# relay1.net
KiCad netlist of a schematic drawn in Altium Designer
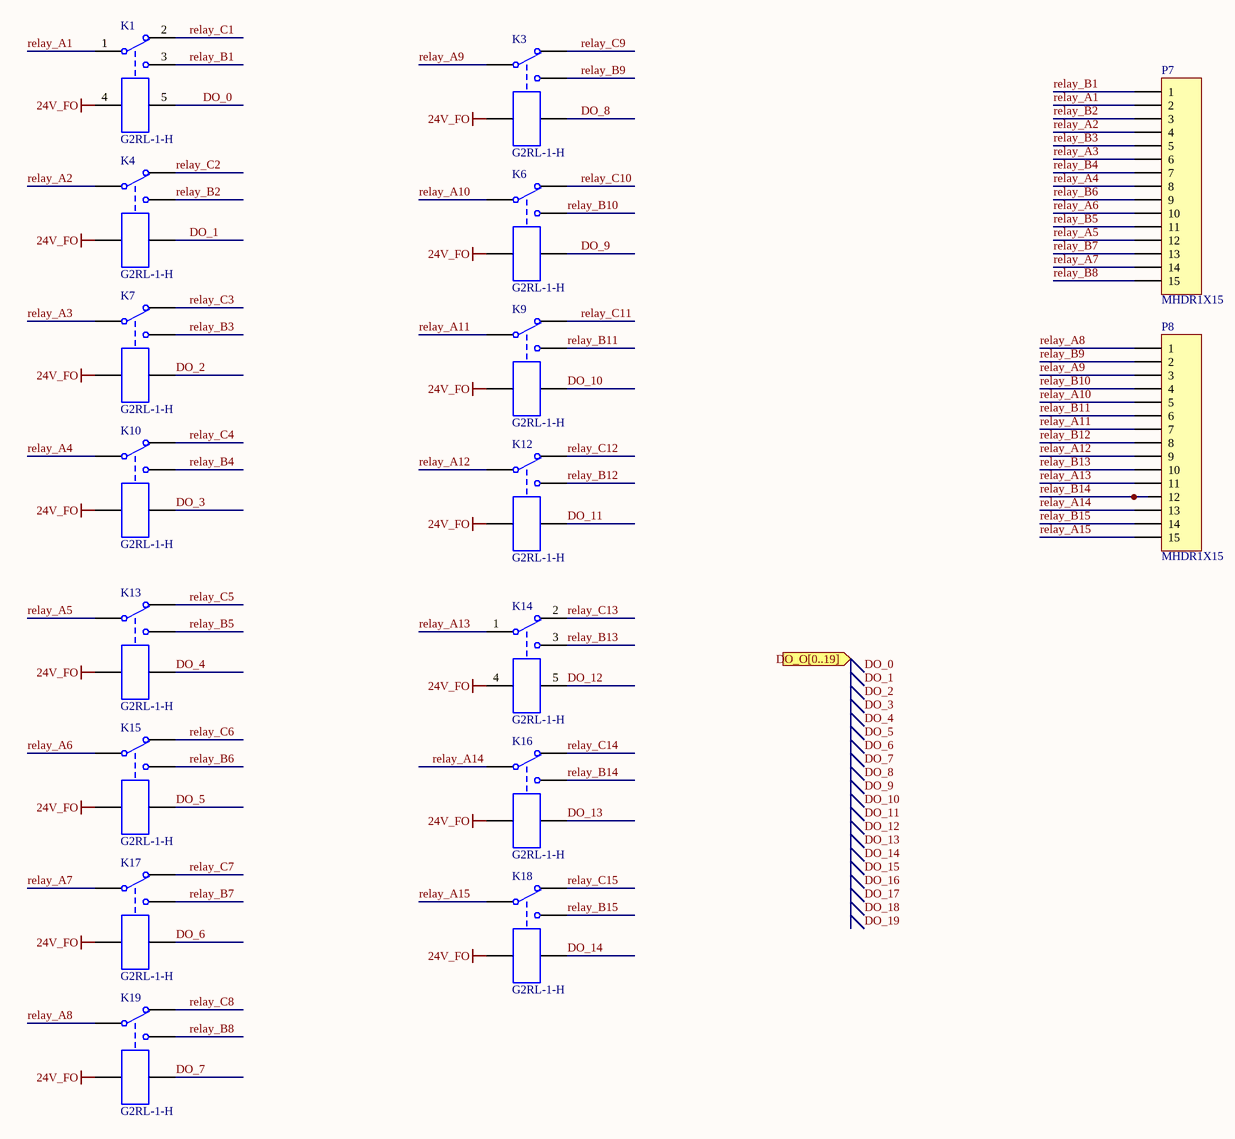
[diagram p0: relay1.SchDoc]

(export (version "E")
  (design (tool "Eeschema 10.0.6"))
  (components
    (comp (ref "K1")
      (value "G2RL-1-H")
      (footprint "G2RL-1-H")
      (description "Single-Pole Dual-Throw Relay")
      (fields (field (name "PUBLISHER") "Altium Limited"))
      (libsource (lib "") (part "Relay-SPDT_1"))
    )
    (comp (ref "K3")
      (value "G2RL-1-H")
      (footprint "G2RL-1-H")
      (description "Single-Pole Dual-Throw Relay")
      (fields (field (name "PUBLISHER") "Altium Limited"))
      (libsource (lib "Miscellaneous Devices") (part "Relay-SPDT"))
    )
    (comp (ref "K4")
      (value "G2RL-1-H")
      (footprint "G2RL-1-H")
      (description "Single-Pole Dual-Throw Relay")
      (fields (field (name "PUBLISHER") "Altium Limited"))
      (libsource (lib "Miscellaneous Devices") (part "Relay-SPDT"))
    )
    (comp (ref "K6")
      (value "G2RL-1-H")
      (footprint "G2RL-1-H")
      (description "Single-Pole Dual-Throw Relay")
      (fields (field (name "PUBLISHER") "Altium Limited"))
      (libsource (lib "Miscellaneous Devices") (part "Relay-SPDT"))
    )
    (comp (ref "K7")
      (value "G2RL-1-H")
      (footprint "G2RL-1-H")
      (description "Single-Pole Dual-Throw Relay")
      (fields (field (name "PUBLISHER") "Altium Limited"))
      (libsource (lib "Miscellaneous Devices") (part "Relay-SPDT"))
    )
    (comp (ref "K9")
      (value "G2RL-1-H")
      (footprint "G2RL-1-H")
      (description "Single-Pole Dual-Throw Relay")
      (fields (field (name "PUBLISHER") "Altium Limited"))
      (libsource (lib "Miscellaneous Devices") (part "Relay-SPDT"))
    )
    (comp (ref "K10")
      (value "G2RL-1-H")
      (footprint "G2RL-1-H")
      (description "Single-Pole Dual-Throw Relay")
      (fields (field (name "PUBLISHER") "Altium Limited"))
      (libsource (lib "Miscellaneous Devices") (part "Relay-SPDT"))
    )
    (comp (ref "K12")
      (value "G2RL-1-H")
      (footprint "G2RL-1-H")
      (description "Single-Pole Dual-Throw Relay")
      (fields (field (name "PUBLISHER") "Altium Limited"))
      (libsource (lib "Miscellaneous Devices") (part "Relay-SPDT"))
    )
    (comp (ref "K13")
      (value "G2RL-1-H")
      (footprint "G2RL-1-H")
      (description "Single-Pole Dual-Throw Relay")
      (fields (field (name "PUBLISHER") "Altium Limited"))
      (libsource (lib "Miscellaneous Devices") (part "Relay-SPDT"))
    )
    (comp (ref "K14")
      (value "G2RL-1-H")
      (footprint "G2RL-1-H")
      (description "Single-Pole Dual-Throw Relay")
      (fields (field (name "PUBLISHER") "Altium Limited"))
      (libsource (lib "") (part "Relay-SPDT_1"))
    )
    (comp (ref "K15")
      (value "G2RL-1-H")
      (footprint "G2RL-1-H")
      (description "Single-Pole Dual-Throw Relay")
      (fields (field (name "PUBLISHER") "Altium Limited"))
      (libsource (lib "Miscellaneous Devices") (part "Relay-SPDT"))
    )
    (comp (ref "K16")
      (value "G2RL-1-H")
      (footprint "G2RL-1-H")
      (description "Single-Pole Dual-Throw Relay")
      (fields (field (name "PUBLISHER") "Altium Limited"))
      (libsource (lib "Miscellaneous Devices") (part "Relay-SPDT"))
    )
    (comp (ref "K17")
      (value "G2RL-1-H")
      (footprint "G2RL-1-H")
      (description "Single-Pole Dual-Throw Relay")
      (fields (field (name "PUBLISHER") "Altium Limited"))
      (libsource (lib "Miscellaneous Devices") (part "Relay-SPDT"))
    )
    (comp (ref "K18")
      (value "G2RL-1-H")
      (footprint "G2RL-1-H")
      (description "Single-Pole Dual-Throw Relay")
      (fields (field (name "PUBLISHER") "Altium Limited"))
      (libsource (lib "Miscellaneous Devices") (part "Relay-SPDT"))
    )
    (comp (ref "K19")
      (value "G2RL-1-H")
      (footprint "G2RL-1-H")
      (description "Single-Pole Dual-Throw Relay")
      (fields (field (name "PUBLISHER") "Altium Limited"))
      (libsource (lib "Miscellaneous Devices") (part "Relay-SPDT"))
    )
    (comp (ref "P7")
      (value "MHDR1X15")
      (footprint "2ETYR-5.08-15P-14-100")
      (description "Header, 15-Pin")
      (fields (field (name "PUBLISHER") "Altium Limited"))
      (libsource (lib "Miscellaneous Connectors") (part "MHDR1X15"))
    )
    (comp (ref "P8")
      (value "MHDR1X15")
      (footprint "2ETYR-5.08-15P-14-100")
      (description "Header, 15-Pin")
      (fields (field (name "PUBLISHER") "Altium Limited"))
      (libsource (lib "Miscellaneous Connectors") (part "MHDR1X15"))
    )
  )
  (nets
    (net (code "21") (name "/DO_0") (class "Default")
      (node (ref "K1") (pin "5") (pinfunction "5_5") (pintype "passive"))
    )
    (net (code "22") (name "/DO_1") (class "Default")
      (node (ref "K4") (pin "5") (pinfunction "5_5") (pintype "passive"))
    )
    (net (code "23") (name "/DO_2") (class "Default")
      (node (ref "K7") (pin "5") (pinfunction "5_5") (pintype "passive"))
    )
    (net (code "24") (name "/DO_3") (class "Default")
      (node (ref "K10") (pin "5") (pinfunction "5_5") (pintype "passive"))
    )
    (net (code "25") (name "/DO_4") (class "Default")
      (node (ref "K13") (pin "5") (pinfunction "5_5") (pintype "passive"))
    )
    (net (code "26") (name "/DO_5") (class "Default")
      (node (ref "K15") (pin "5") (pinfunction "5_5") (pintype "passive"))
    )
    (net (code "27") (name "/DO_6") (class "Default")
      (node (ref "K17") (pin "5") (pinfunction "5_5") (pintype "passive"))
    )
    (net (code "28") (name "/DO_7") (class "Default")
      (node (ref "K19") (pin "5") (pinfunction "5_5") (pintype "passive"))
    )
    (net (code "29") (name "/DO_8") (class "Default")
      (node (ref "K3") (pin "5") (pinfunction "5_5") (pintype "passive"))
    )
    (net (code "30") (name "/DO_9") (class "Default")
      (node (ref "K6") (pin "5") (pinfunction "5_5") (pintype "passive"))
    )
    (net (code "31") (name "/DO_10") (class "Default")
      (node (ref "K9") (pin "5") (pinfunction "5_5") (pintype "passive"))
    )
    (net (code "32") (name "/DO_11") (class "Default")
      (node (ref "K12") (pin "5") (pinfunction "5_5") (pintype "passive"))
    )
    (net (code "33") (name "/DO_12") (class "Default")
      (node (ref "K14") (pin "5") (pinfunction "5_5") (pintype "passive"))
    )
    (net (code "34") (name "/DO_13") (class "Default")
      (node (ref "K16") (pin "5") (pinfunction "5_5") (pintype "passive"))
    )
    (net (code "35") (name "/DO_14") (class "Default")
      (node (ref "K18") (pin "5") (pinfunction "5_5") (pintype "passive"))
    )
    (net (code "42") (name "/relay_A1") (class "Default")
      (node (ref "K1") (pin "1") (pinfunction "1_1") (pintype "passive"))
      (node (ref "P7") (pin "2") (pinfunction "2_2") (pintype "passive"))
    )
    (net (code "43") (name "/relay_A2") (class "Default")
      (node (ref "K4") (pin "1") (pinfunction "1_1") (pintype "passive"))
      (node (ref "P7") (pin "4") (pinfunction "4_4") (pintype "passive"))
    )
    (net (code "44") (name "/relay_A3") (class "Default")
      (node (ref "K7") (pin "1") (pinfunction "1_1") (pintype "passive"))
      (node (ref "P7") (pin "6") (pinfunction "6_6") (pintype "passive"))
    )
    (net (code "45") (name "/relay_A4") (class "Default")
      (node (ref "K10") (pin "1") (pinfunction "1_1") (pintype "passive"))
      (node (ref "P7") (pin "8") (pinfunction "8_8") (pintype "passive"))
    )
    (net (code "46") (name "/relay_A5") (class "Default")
      (node (ref "K13") (pin "1") (pinfunction "1_1") (pintype "passive"))
      (node (ref "P7") (pin "12") (pinfunction "12_12") (pintype "passive"))
    )
    (net (code "47") (name "/relay_A6") (class "Default")
      (node (ref "K15") (pin "1") (pinfunction "1_1") (pintype "passive"))
      (node (ref "P7") (pin "10") (pinfunction "10_10") (pintype "passive"))
    )
    (net (code "48") (name "/relay_A7") (class "Default")
      (node (ref "K17") (pin "1") (pinfunction "1_1") (pintype "passive"))
      (node (ref "P7") (pin "14") (pinfunction "14_14") (pintype "passive"))
    )
    (net (code "49") (name "/relay_A8") (class "Default")
      (node (ref "K19") (pin "1") (pinfunction "1_1") (pintype "passive"))
      (node (ref "P8") (pin "1") (pinfunction "1_1") (pintype "passive"))
    )
    (net (code "50") (name "/relay_A9") (class "Default")
      (node (ref "K3") (pin "1") (pinfunction "1_1") (pintype "passive"))
      (node (ref "P8") (pin "3") (pinfunction "3_3") (pintype "passive"))
    )
    (net (code "51") (name "/relay_A10") (class "Default")
      (node (ref "K6") (pin "1") (pinfunction "1_1") (pintype "passive"))
      (node (ref "P8") (pin "5") (pinfunction "5_5") (pintype "passive"))
    )
    (net (code "52") (name "/relay_A11") (class "Default")
      (node (ref "K9") (pin "1") (pinfunction "1_1") (pintype "passive"))
      (node (ref "P8") (pin "7") (pinfunction "7_7") (pintype "passive"))
    )
    (net (code "53") (name "/relay_A12") (class "Default")
      (node (ref "K12") (pin "1") (pinfunction "1_1") (pintype "passive"))
      (node (ref "P8") (pin "9") (pinfunction "9_9") (pintype "passive"))
    )
    (net (code "54") (name "/relay_A13") (class "Default")
      (node (ref "K14") (pin "1") (pinfunction "1_1") (pintype "passive"))
      (node (ref "P8") (pin "11") (pinfunction "11_11") (pintype "passive"))
    )
    (net (code "55") (name "/relay_A14") (class "Default")
      (node (ref "K16") (pin "1") (pinfunction "1_1") (pintype "passive"))
      (node (ref "P8") (pin "13") (pinfunction "13_13") (pintype "passive"))
    )
    (net (code "56") (name "/relay_A15") (class "Default")
      (node (ref "K18") (pin "1") (pinfunction "1_1") (pintype "passive"))
      (node (ref "P8") (pin "15") (pinfunction "15_15") (pintype "passive"))
    )
    (net (code "57") (name "/relay_B1") (class "Default")
      (node (ref "K1") (pin "3") (pinfunction "3_3") (pintype "passive"))
      (node (ref "P7") (pin "1") (pinfunction "1_1") (pintype "passive"))
    )
    (net (code "58") (name "/relay_B2") (class "Default")
      (node (ref "K4") (pin "3") (pinfunction "3_3") (pintype "passive"))
      (node (ref "P7") (pin "3") (pinfunction "3_3") (pintype "passive"))
    )
    (net (code "59") (name "/relay_B3") (class "Default")
      (node (ref "K7") (pin "3") (pinfunction "3_3") (pintype "passive"))
      (node (ref "P7") (pin "5") (pinfunction "5_5") (pintype "passive"))
    )
    (net (code "60") (name "/relay_B4") (class "Default")
      (node (ref "K10") (pin "3") (pinfunction "3_3") (pintype "passive"))
      (node (ref "P7") (pin "7") (pinfunction "7_7") (pintype "passive"))
    )
    (net (code "61") (name "/relay_B5") (class "Default")
      (node (ref "K13") (pin "3") (pinfunction "3_3") (pintype "passive"))
      (node (ref "P7") (pin "11") (pinfunction "11_11") (pintype "passive"))
    )
    (net (code "62") (name "/relay_B6") (class "Default")
      (node (ref "K15") (pin "3") (pinfunction "3_3") (pintype "passive"))
      (node (ref "P7") (pin "9") (pinfunction "9_9") (pintype "passive"))
    )
    (net (code "63") (name "/relay_B7") (class "Default")
      (node (ref "K17") (pin "3") (pinfunction "3_3") (pintype "passive"))
      (node (ref "P7") (pin "13") (pinfunction "13_13") (pintype "passive"))
    )
    (net (code "64") (name "/relay_B8") (class "Default")
      (node (ref "K19") (pin "3") (pinfunction "3_3") (pintype "passive"))
      (node (ref "P7") (pin "15") (pinfunction "15_15") (pintype "passive"))
    )
    (net (code "65") (name "/relay_B9") (class "Default")
      (node (ref "K3") (pin "3") (pinfunction "3_3") (pintype "passive"))
      (node (ref "P8") (pin "2") (pinfunction "2_2") (pintype "passive"))
    )
    (net (code "66") (name "/relay_B10") (class "Default")
      (node (ref "K6") (pin "3") (pinfunction "3_3") (pintype "passive"))
      (node (ref "P8") (pin "4") (pinfunction "4_4") (pintype "passive"))
    )
    (net (code "67") (name "/relay_B11") (class "Default")
      (node (ref "K9") (pin "3") (pinfunction "3_3") (pintype "passive"))
      (node (ref "P8") (pin "6") (pinfunction "6_6") (pintype "passive"))
    )
    (net (code "68") (name "/relay_B12") (class "Default")
      (node (ref "K12") (pin "3") (pinfunction "3_3") (pintype "passive"))
      (node (ref "P8") (pin "8") (pinfunction "8_8") (pintype "passive"))
    )
    (net (code "69") (name "/relay_B13") (class "Default")
      (node (ref "K14") (pin "3") (pinfunction "3_3") (pintype "passive"))
      (node (ref "P8") (pin "10") (pinfunction "10_10") (pintype "passive"))
    )
    (net (code "70") (name "/relay_B14") (class "Default")
      (node (ref "K16") (pin "3") (pinfunction "3_3") (pintype "passive"))
      (node (ref "P8") (pin "12") (pinfunction "12_12") (pintype "passive"))
    )
    (net (code "71") (name "/relay_B15") (class "Default")
      (node (ref "K18") (pin "3") (pinfunction "3_3") (pintype "passive"))
      (node (ref "P8") (pin "14") (pinfunction "14_14") (pintype "passive"))
    )
    (net (code "72") (name "/relay_C1") (class "Default")
      (node (ref "K1") (pin "2") (pinfunction "2_2") (pintype "passive"))
    )
    (net (code "73") (name "/relay_C2") (class "Default")
      (node (ref "K4") (pin "2") (pinfunction "2_2") (pintype "passive"))
    )
    (net (code "74") (name "/relay_C3") (class "Default")
      (node (ref "K7") (pin "2") (pinfunction "2_2") (pintype "passive"))
    )
    (net (code "75") (name "/relay_C4") (class "Default")
      (node (ref "K10") (pin "2") (pinfunction "2_2") (pintype "passive"))
    )
    (net (code "76") (name "/relay_C5") (class "Default")
      (node (ref "K13") (pin "2") (pinfunction "2_2") (pintype "passive"))
    )
    (net (code "77") (name "/relay_C6") (class "Default")
      (node (ref "K15") (pin "2") (pinfunction "2_2") (pintype "passive"))
    )
    (net (code "78") (name "/relay_C7") (class "Default")
      (node (ref "K17") (pin "2") (pinfunction "2_2") (pintype "passive"))
    )
    (net (code "79") (name "/relay_C8") (class "Default")
      (node (ref "K19") (pin "2") (pinfunction "2_2") (pintype "passive"))
    )
    (net (code "80") (name "/relay_C9") (class "Default")
      (node (ref "K3") (pin "2") (pinfunction "2_2") (pintype "passive"))
    )
    (net (code "81") (name "/relay_C10") (class "Default")
      (node (ref "K6") (pin "2") (pinfunction "2_2") (pintype "passive"))
    )
    (net (code "82") (name "/relay_C11") (class "Default")
      (node (ref "K9") (pin "2") (pinfunction "2_2") (pintype "passive"))
    )
    (net (code "83") (name "/relay_C12") (class "Default")
      (node (ref "K12") (pin "2") (pinfunction "2_2") (pintype "passive"))
    )
    (net (code "84") (name "/relay_C13") (class "Default")
      (node (ref "K14") (pin "2") (pinfunction "2_2") (pintype "passive"))
    )
    (net (code "85") (name "/relay_C14") (class "Default")
      (node (ref "K16") (pin "2") (pinfunction "2_2") (pintype "passive"))
    )
    (net (code "86") (name "/relay_C15") (class "Default")
      (node (ref "K18") (pin "2") (pinfunction "2_2") (pintype "passive"))
    )
    (net (code "87") (name "24V_FO") (class "Default")
      (node (ref "K1") (pin "4") (pinfunction "4_4") (pintype "passive"))
      (node (ref "K10") (pin "4") (pinfunction "4_4") (pintype "passive"))
      (node (ref "K12") (pin "4") (pinfunction "4_4") (pintype "passive"))
      (node (ref "K13") (pin "4") (pinfunction "4_4") (pintype "passive"))
      (node (ref "K14") (pin "4") (pinfunction "4_4") (pintype "passive"))
      (node (ref "K15") (pin "4") (pinfunction "4_4") (pintype "passive"))
      (node (ref "K16") (pin "4") (pinfunction "4_4") (pintype "passive"))
      (node (ref "K17") (pin "4") (pinfunction "4_4") (pintype "passive"))
      (node (ref "K18") (pin "4") (pinfunction "4_4") (pintype "passive"))
      (node (ref "K19") (pin "4") (pinfunction "4_4") (pintype "passive"))
      (node (ref "K3") (pin "4") (pinfunction "4_4") (pintype "passive"))
      (node (ref "K4") (pin "4") (pinfunction "4_4") (pintype "passive"))
      (node (ref "K6") (pin "4") (pinfunction "4_4") (pintype "passive"))
      (node (ref "K7") (pin "4") (pinfunction "4_4") (pintype "passive"))
      (node (ref "K9") (pin "4") (pinfunction "4_4") (pintype "passive"))
    )
  )
)
